# LinPsu.net
KiCad netlist of a schematic drawn in EAGLE
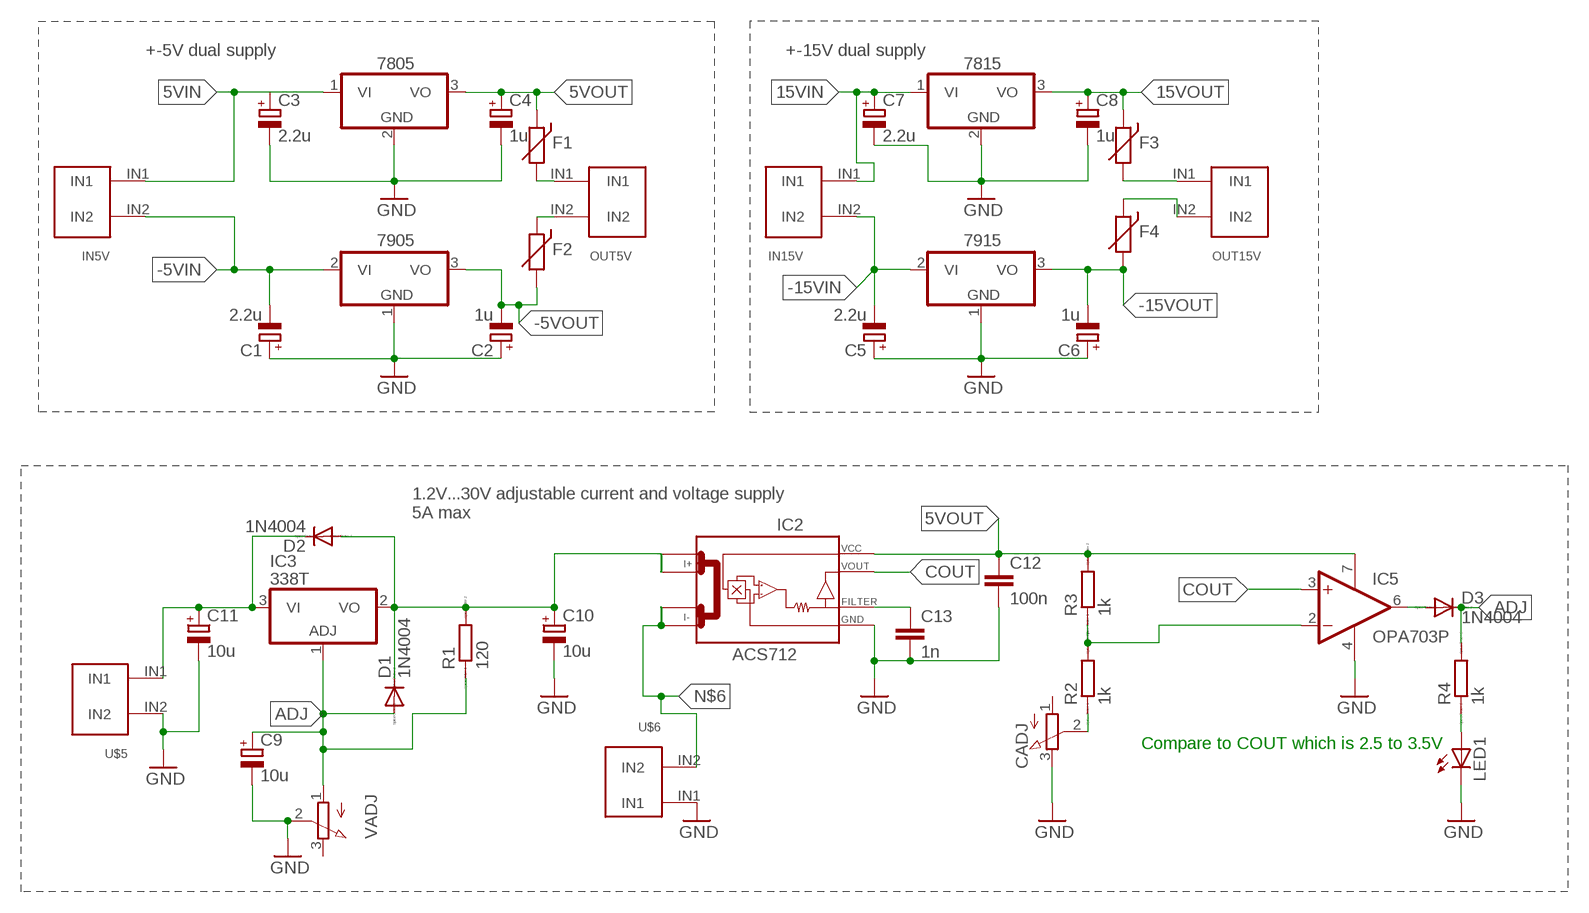
[diagram p0: schematic, sheet 1]

(export (version "E")
  (design (tool "Eeschema 10.0.6"))
  (components
    (comp (ref "7805")
      (value "7805")
      (footprint "eagle-import:TO220H")
      (libsource (lib "eagle-import") (part "78T15"))
    )
    (comp (ref "7815")
      (value "7815T")
      (footprint "eagle-import:TO220H")
      (libsource (lib "eagle-import") (part "78T15"))
    )
    (comp (ref "7905")
      (value "7905T")
      (footprint "eagle-import:TO220H")
      (libsource (lib "eagle-import") (part "79T05"))
    )
    (comp (ref "7915")
      (value "7915T")
      (footprint "eagle-import:TO220H")
      (libsource (lib "eagle-import") (part "79T15"))
    )
    (comp (ref "C1")
      (value "2.2u")
      (footprint "eagle-import:E5-5")
      (libsource (lib "eagle-import") (part "CPOL-EUE5-5"))
    )
    (comp (ref "C2")
      (value "1u")
      (footprint "eagle-import:E5-4")
      (libsource (lib "eagle-import") (part "CPOL-EUE5-4"))
    )
    (comp (ref "C3")
      (value "2.2u")
      (footprint "eagle-import:E5-5")
      (libsource (lib "eagle-import") (part "CPOL-EUE5-5"))
    )
    (comp (ref "C4")
      (value "1u")
      (footprint "eagle-import:E5-4")
      (libsource (lib "eagle-import") (part "CPOL-EUE5-4"))
    )
    (comp (ref "C5")
      (value "2.2u")
      (footprint "eagle-import:E5-5")
      (libsource (lib "eagle-import") (part "CPOL-EUE5-5"))
    )
    (comp (ref "C6")
      (value "1u")
      (footprint "eagle-import:E5-4")
      (libsource (lib "eagle-import") (part "CPOL-EUE5-4"))
    )
    (comp (ref "C7")
      (value "2.2u")
      (footprint "eagle-import:E5-5")
      (libsource (lib "eagle-import") (part "CPOL-EUE5-5"))
    )
    (comp (ref "C8")
      (value "1u")
      (footprint "eagle-import:E5-4")
      (libsource (lib "eagle-import") (part "CPOL-EUE5-4"))
    )
    (comp (ref "C9")
      (value "10u")
      (footprint "eagle-import:E5-5")
      (libsource (lib "eagle-import") (part "CPOL-EUE5-5"))
    )
    (comp (ref "C10")
      (value "10u")
      (footprint "eagle-import:E5-5")
      (libsource (lib "eagle-import") (part "CPOL-EUE5-5"))
    )
    (comp (ref "C11")
      (value "10u")
      (footprint "eagle-import:E5-5")
      (libsource (lib "eagle-import") (part "CPOL-EUE5-5"))
    )
    (comp (ref "C12")
      (value "100n")
      (footprint "eagle-import:C2.5-4")
      (libsource (lib "eagle-import") (part "C2.5/4"))
    )
    (comp (ref "C13")
      (value "1n")
      (footprint "eagle-import:C2.5-4")
      (libsource (lib "eagle-import") (part "C2.5/4"))
    )
    (comp (ref "CADJ")
      (value "3RP/1610N")
      (footprint "eagle-import:3RP_1610N")
      (libsource (lib "eagle-import") (part "3RP/1610N"))
    )
    (comp (ref "D1")
      (value "1N4004")
      (footprint "eagle-import:DO41-10")
      (libsource (lib "eagle-import") (part "1N4004"))
    )
    (comp (ref "D2")
      (value "1N4004")
      (footprint "eagle-import:DO41-10")
      (libsource (lib "eagle-import") (part "1N4004"))
    )
    (comp (ref "D3")
      (value "1N4004")
      (footprint "eagle-import:DO41-10")
      (libsource (lib "eagle-import") (part "1N4004"))
    )
    (comp (ref "F1")
      (value "THERMISTOR-5")
      (footprint "eagle-import:R-5")
      (libsource (lib "eagle-import") (part "THERMISTOR-5"))
    )
    (comp (ref "F2")
      (value "THERMISTOR-5")
      (footprint "eagle-import:R-5")
      (libsource (lib "eagle-import") (part "THERMISTOR-5"))
    )
    (comp (ref "F3")
      (value "THERMISTOR-5")
      (footprint "eagle-import:R-5")
      (libsource (lib "eagle-import") (part "THERMISTOR-5"))
    )
    (comp (ref "F4")
      (value "THERMISTOR-5")
      (footprint "eagle-import:R-5")
      (libsource (lib "eagle-import") (part "THERMISTOR-5"))
    )
    (comp (ref "IC2")
      (value "ACS712")
      (footprint "eagle-import:SO08")
      (libsource (lib "eagle-import") (part "ACS712"))
    )
    (comp (ref "IC3")
      (value "338T")
      (footprint "eagle-import:TO220H")
      (libsource (lib "eagle-import") (part "317T"))
    )
    (comp (ref "IC5")
      (value "OPA703P")
      (footprint "eagle-import:DIL08")
      (libsource (lib "eagle-import") (part "OPA743P"))
    )
    (comp (ref "IN5V")
      (value "1X2_5MM")
      (footprint "eagle-import:1X2_5MM")
      (libsource (lib "eagle-import") (part "1X2_5MM"))
    )
    (comp (ref "IN15V")
      (value "1X2_5MM")
      (footprint "eagle-import:1X2_5MM")
      (libsource (lib "eagle-import") (part "1X2_5MM"))
    )
    (comp (ref "LED1")
      (value "LED3MM")
      (footprint "eagle-import:LED3MM")
      (libsource (lib "eagle-import") (part "LED3MM"))
    )
    (comp (ref "OUT5V")
      (value "1X2_5MM")
      (footprint "eagle-import:1X2_5MM")
      (libsource (lib "eagle-import") (part "1X2_5MM"))
    )
    (comp (ref "OUT15V")
      (value "1X2_5MM")
      (footprint "eagle-import:1X2_5MM")
      (libsource (lib "eagle-import") (part "1X2_5MM"))
    )
    (comp (ref "R1")
      (value "120")
      (footprint "eagle-import:0207_10")
      (libsource (lib "eagle-import") (part "R0207/10"))
    )
    (comp (ref "R2")
      (value "1k")
      (footprint "eagle-import:0207_10")
      (libsource (lib "eagle-import") (part "R0207/10"))
    )
    (comp (ref "R3")
      (value "1k")
      (footprint "eagle-import:0207_10")
      (libsource (lib "eagle-import") (part "R0207/10"))
    )
    (comp (ref "R4")
      (value "1k")
      (footprint "eagle-import:0207_10")
      (libsource (lib "eagle-import") (part "R0207/10"))
    )
    (comp (ref "U$5")
      (value "1X2_5MM")
      (footprint "eagle-import:1X2_5MM")
      (libsource (lib "eagle-import") (part "1X2_5MM"))
    )
    (comp (ref "U$6")
      (value "1X2_5MM")
      (footprint "eagle-import:1X2_5MM")
      (libsource (lib "eagle-import") (part "1X2_5MM"))
    )
    (comp (ref "VADJ")
      (value "3RP/1610N")
      (footprint "eagle-import:3RP_1610N")
      (libsource (lib "eagle-import") (part "3RP/1610N"))
    )
  )
  (nets
    (net (code "1") (name "-5VIN") (class "Default")
      (node (ref "7905") (pin "2") (pinfunction "VI_2") (pintype "input"))
      (node (ref "C1") (pin "-") (pinfunction "-_-") (pintype "passive"))
      (node (ref "IN5V") (pin "IN2") (pinfunction "IN2_IN2") (pintype "bidirectional"))
    )
    (net (code "2") (name "-5VOUT") (class "Default")
      (node (ref "7905") (pin "3") (pinfunction "VO_3") (pintype "passive"))
      (node (ref "C2") (pin "-") (pinfunction "-_-") (pintype "passive"))
      (node (ref "F2") (pin "2") (pinfunction "2_2") (pintype "passive"))
    )
    (net (code "3") (name "-15VIN") (class "Default")
      (node (ref "7915") (pin "2") (pinfunction "VI_2") (pintype "input"))
      (node (ref "C5") (pin "-") (pinfunction "-_-") (pintype "passive"))
      (node (ref "IN15V") (pin "IN2") (pinfunction "IN2_IN2") (pintype "bidirectional"))
    )
    (net (code "4") (name "-15VOUT") (class "Default")
      (node (ref "7915") (pin "3") (pinfunction "VO_3") (pintype "passive"))
      (node (ref "C6") (pin "-") (pinfunction "-_-") (pintype "passive"))
      (node (ref "F4") (pin "2") (pinfunction "2_2") (pintype "passive"))
    )
    (net (code "5") (name "5VIN") (class "Default")
      (node (ref "7805") (pin "1") (pinfunction "VI_1") (pintype "input"))
      (node (ref "C3") (pin "+") (pinfunction "+_+") (pintype "passive"))
      (node (ref "IN5V") (pin "IN1") (pinfunction "IN1_IN1") (pintype "bidirectional"))
    )
    (net (code "6") (name "5VOUT") (class "Default")
      (node (ref "7805") (pin "3") (pinfunction "VO_3") (pintype "passive"))
      (node (ref "C12") (pin "1") (pinfunction "1_1") (pintype "passive"))
      (node (ref "C4") (pin "+") (pinfunction "+_+") (pintype "passive"))
      (node (ref "F1") (pin "1") (pinfunction "1_1") (pintype "passive"))
      (node (ref "IC2") (pin "8") (pinfunction "VCC_8") (pintype "power_in"))
      (node (ref "IC5") (pin "7") (pinfunction "V+_7") (pintype "power_in"))
      (node (ref "R3") (pin "2") (pinfunction "2_2") (pintype "passive"))
    )
    (net (code "7") (name "15VIN") (class "Default")
      (node (ref "7815") (pin "1") (pinfunction "VI_1") (pintype "input"))
      (node (ref "C7") (pin "+") (pinfunction "+_+") (pintype "passive"))
      (node (ref "IN15V") (pin "IN1") (pinfunction "IN1_IN1") (pintype "bidirectional"))
    )
    (net (code "8") (name "15VOUT") (class "Default")
      (node (ref "7815") (pin "3") (pinfunction "VO_3") (pintype "passive"))
      (node (ref "C8") (pin "+") (pinfunction "+_+") (pintype "passive"))
      (node (ref "F3") (pin "1") (pinfunction "1_1") (pintype "passive"))
    )
    (net (code "9") (name "ADJ") (class "Default")
      (node (ref "C9") (pin "+") (pinfunction "+_+") (pintype "passive"))
      (node (ref "D1") (pin "A") (pinfunction "A_A") (pintype "passive"))
      (node (ref "D3") (pin "C") (pinfunction "C_C") (pintype "passive"))
      (node (ref "IC3") (pin "1") (pinfunction "ADJ_1") (pintype "input"))
      (node (ref "R1") (pin "1") (pinfunction "1_1") (pintype "passive"))
      (node (ref "R4") (pin "2") (pinfunction "2_2") (pintype "passive"))
      (node (ref "VADJ") (pin "1") (pinfunction "A_1") (pintype "passive"))
    )
    (net (code "10") (name "COUT") (class "Default")
      (node (ref "IC2") (pin "7") (pinfunction "VOUT_7") (pintype "output"))
      (node (ref "IC5") (pin "3") (pinfunction "+IN_3") (pintype "input"))
    )
    (net (code "11") (name "GND") (class "Default")
      (node (ref "7805") (pin "2") (pinfunction "GND_2") (pintype "passive"))
      (node (ref "7815") (pin "2") (pinfunction "GND_2") (pintype "passive"))
      (node (ref "7905") (pin "1") (pinfunction "GND_1") (pintype "passive"))
      (node (ref "7915") (pin "1") (pinfunction "GND_1") (pintype "passive"))
      (node (ref "C1") (pin "+") (pinfunction "+_+") (pintype "passive"))
      (node (ref "C10") (pin "-") (pinfunction "-_-") (pintype "passive"))
      (node (ref "C11") (pin "-") (pinfunction "-_-") (pintype "passive"))
      (node (ref "C12") (pin "2") (pinfunction "2_2") (pintype "passive"))
      (node (ref "C13") (pin "2") (pinfunction "2_2") (pintype "passive"))
      (node (ref "C2") (pin "+") (pinfunction "+_+") (pintype "passive"))
      (node (ref "C3") (pin "-") (pinfunction "-_-") (pintype "passive"))
      (node (ref "C4") (pin "-") (pinfunction "-_-") (pintype "passive"))
      (node (ref "C5") (pin "+") (pinfunction "+_+") (pintype "passive"))
      (node (ref "C6") (pin "+") (pinfunction "+_+") (pintype "passive"))
      (node (ref "C7") (pin "-") (pinfunction "-_-") (pintype "passive"))
      (node (ref "C8") (pin "-") (pinfunction "-_-") (pintype "passive"))
      (node (ref "C9") (pin "-") (pinfunction "-_-") (pintype "passive"))
      (node (ref "CADJ") (pin "3") (pinfunction "E_3") (pintype "passive"))
      (node (ref "IC2") (pin "5") (pinfunction "GND_5") (pintype "power_in"))
      (node (ref "IC5") (pin "4") (pinfunction "V-_4") (pintype "power_in"))
      (node (ref "LED1") (pin "K") (pinfunction "C_K") (pintype "passive"))
      (node (ref "U$5") (pin "IN2") (pinfunction "IN2_IN2") (pintype "bidirectional"))
      (node (ref "U$6") (pin "IN1") (pinfunction "IN1_IN1") (pintype "bidirectional"))
      (node (ref "VADJ") (pin "2") (pinfunction "S_2") (pintype "passive"))
    )
    (net (code "12") (name "N$6") (class "Default")
      (node (ref "IC2") (pin "3") (pinfunction "I-_0_3") (pintype "bidirectional"))
      (node (ref "IC2") (pin "4") (pinfunction "I-_1_4") (pintype "bidirectional"))
      (node (ref "U$6") (pin "IN2") (pinfunction "IN2_IN2") (pintype "bidirectional"))
    )
    (net (code "13") (name "Net-(CADJ-S)") (class "Default")
      (node (ref "CADJ") (pin "2") (pinfunction "S_2") (pintype "passive"))
      (node (ref "R2") (pin "1") (pinfunction "1_1") (pintype "passive"))
    )
    (net (code "14") (name "Net-(F1-Pad2)") (class "Default")
      (node (ref "F1") (pin "2") (pinfunction "2_2") (pintype "passive"))
      (node (ref "OUT5V") (pin "IN1") (pinfunction "IN1_IN1") (pintype "bidirectional"))
    )
    (net (code "15") (name "Net-(F2-Pad1)") (class "Default")
      (node (ref "F2") (pin "1") (pinfunction "1_1") (pintype "passive"))
      (node (ref "OUT5V") (pin "IN2") (pinfunction "IN2_IN2") (pintype "bidirectional"))
    )
    (net (code "16") (name "Net-(F3-Pad2)") (class "Default")
      (node (ref "F3") (pin "2") (pinfunction "2_2") (pintype "passive"))
      (node (ref "OUT15V") (pin "IN1") (pinfunction "IN1_IN1") (pintype "bidirectional"))
    )
    (net (code "17") (name "Net-(F4-Pad1)") (class "Default")
      (node (ref "F4") (pin "1") (pinfunction "1_1") (pintype "passive"))
      (node (ref "OUT15V") (pin "IN2") (pinfunction "IN2_IN2") (pintype "bidirectional"))
    )
    (net (code "18") (name "Net-(IC2-FILTER)") (class "Default")
      (node (ref "C13") (pin "1") (pinfunction "1_1") (pintype "passive"))
      (node (ref "IC2") (pin "6") (pinfunction "FILTER_6") (pintype "bidirectional"))
    )
    (net (code "19") (name "Net-(IC2-I+_0)") (class "Default")
      (node (ref "C10") (pin "+") (pinfunction "+_+") (pintype "passive"))
      (node (ref "D1") (pin "C") (pinfunction "C_C") (pintype "passive"))
      (node (ref "D2") (pin "A") (pinfunction "A_A") (pintype "passive"))
      (node (ref "IC2") (pin "1") (pinfunction "I+_0_1") (pintype "bidirectional"))
      (node (ref "IC3") (pin "2") (pinfunction "VO_2") (pintype "passive"))
      (node (ref "R1") (pin "2") (pinfunction "2_2") (pintype "passive"))
    )
    (net (code "20") (name "Net-(IC3-VI)") (class "Default")
      (node (ref "C11") (pin "+") (pinfunction "+_+") (pintype "passive"))
      (node (ref "D2") (pin "C") (pinfunction "C_C") (pintype "passive"))
      (node (ref "IC3") (pin "3") (pinfunction "VI_3") (pintype "input"))
      (node (ref "U$5") (pin "IN1") (pinfunction "IN1_IN1") (pintype "bidirectional"))
    )
    (net (code "21") (name "Net-(IC5--IN)") (class "Default")
      (node (ref "IC5") (pin "2") (pinfunction "-IN_2") (pintype "input"))
      (node (ref "R2") (pin "2") (pinfunction "2_2") (pintype "passive"))
      (node (ref "R3") (pin "1") (pinfunction "1_1") (pintype "passive"))
    )
    (net (code "22") (name "Net-(IC5-OUT)") (class "Default")
      (node (ref "D3") (pin "A") (pinfunction "A_A") (pintype "passive"))
      (node (ref "IC5") (pin "6") (pinfunction "OUT_6") (pintype "output"))
    )
    (net (code "23") (name "Net-(LED1-PadA)") (class "Default")
      (node (ref "LED1") (pin "A") (pinfunction "A_A") (pintype "passive"))
      (node (ref "R4") (pin "1") (pinfunction "1_1") (pintype "passive"))
    )
    (net (code "24") (name "unconnected-(CADJ-A-Pad1)") (class "Default")
      (node (ref "CADJ") (pin "1") (pinfunction "A_1") (pintype "passive"))
    )
    (net (code "25") (name "unconnected-(IC2-I+_1-Pad2)") (class "Default")
      (node (ref "IC2") (pin "2") (pinfunction "I+_1_2") (pintype "bidirectional"))
    )
    (net (code "26") (name "unconnected-(VADJ-E-Pad3)") (class "Default")
      (node (ref "VADJ") (pin "3") (pinfunction "E_3") (pintype "passive"))
    )
  )
)
